# SCH_GSME_voltmeter_Arduino_ESP8266_TP405.net
KiCad netlist of a schematic drawn in EasyEDA
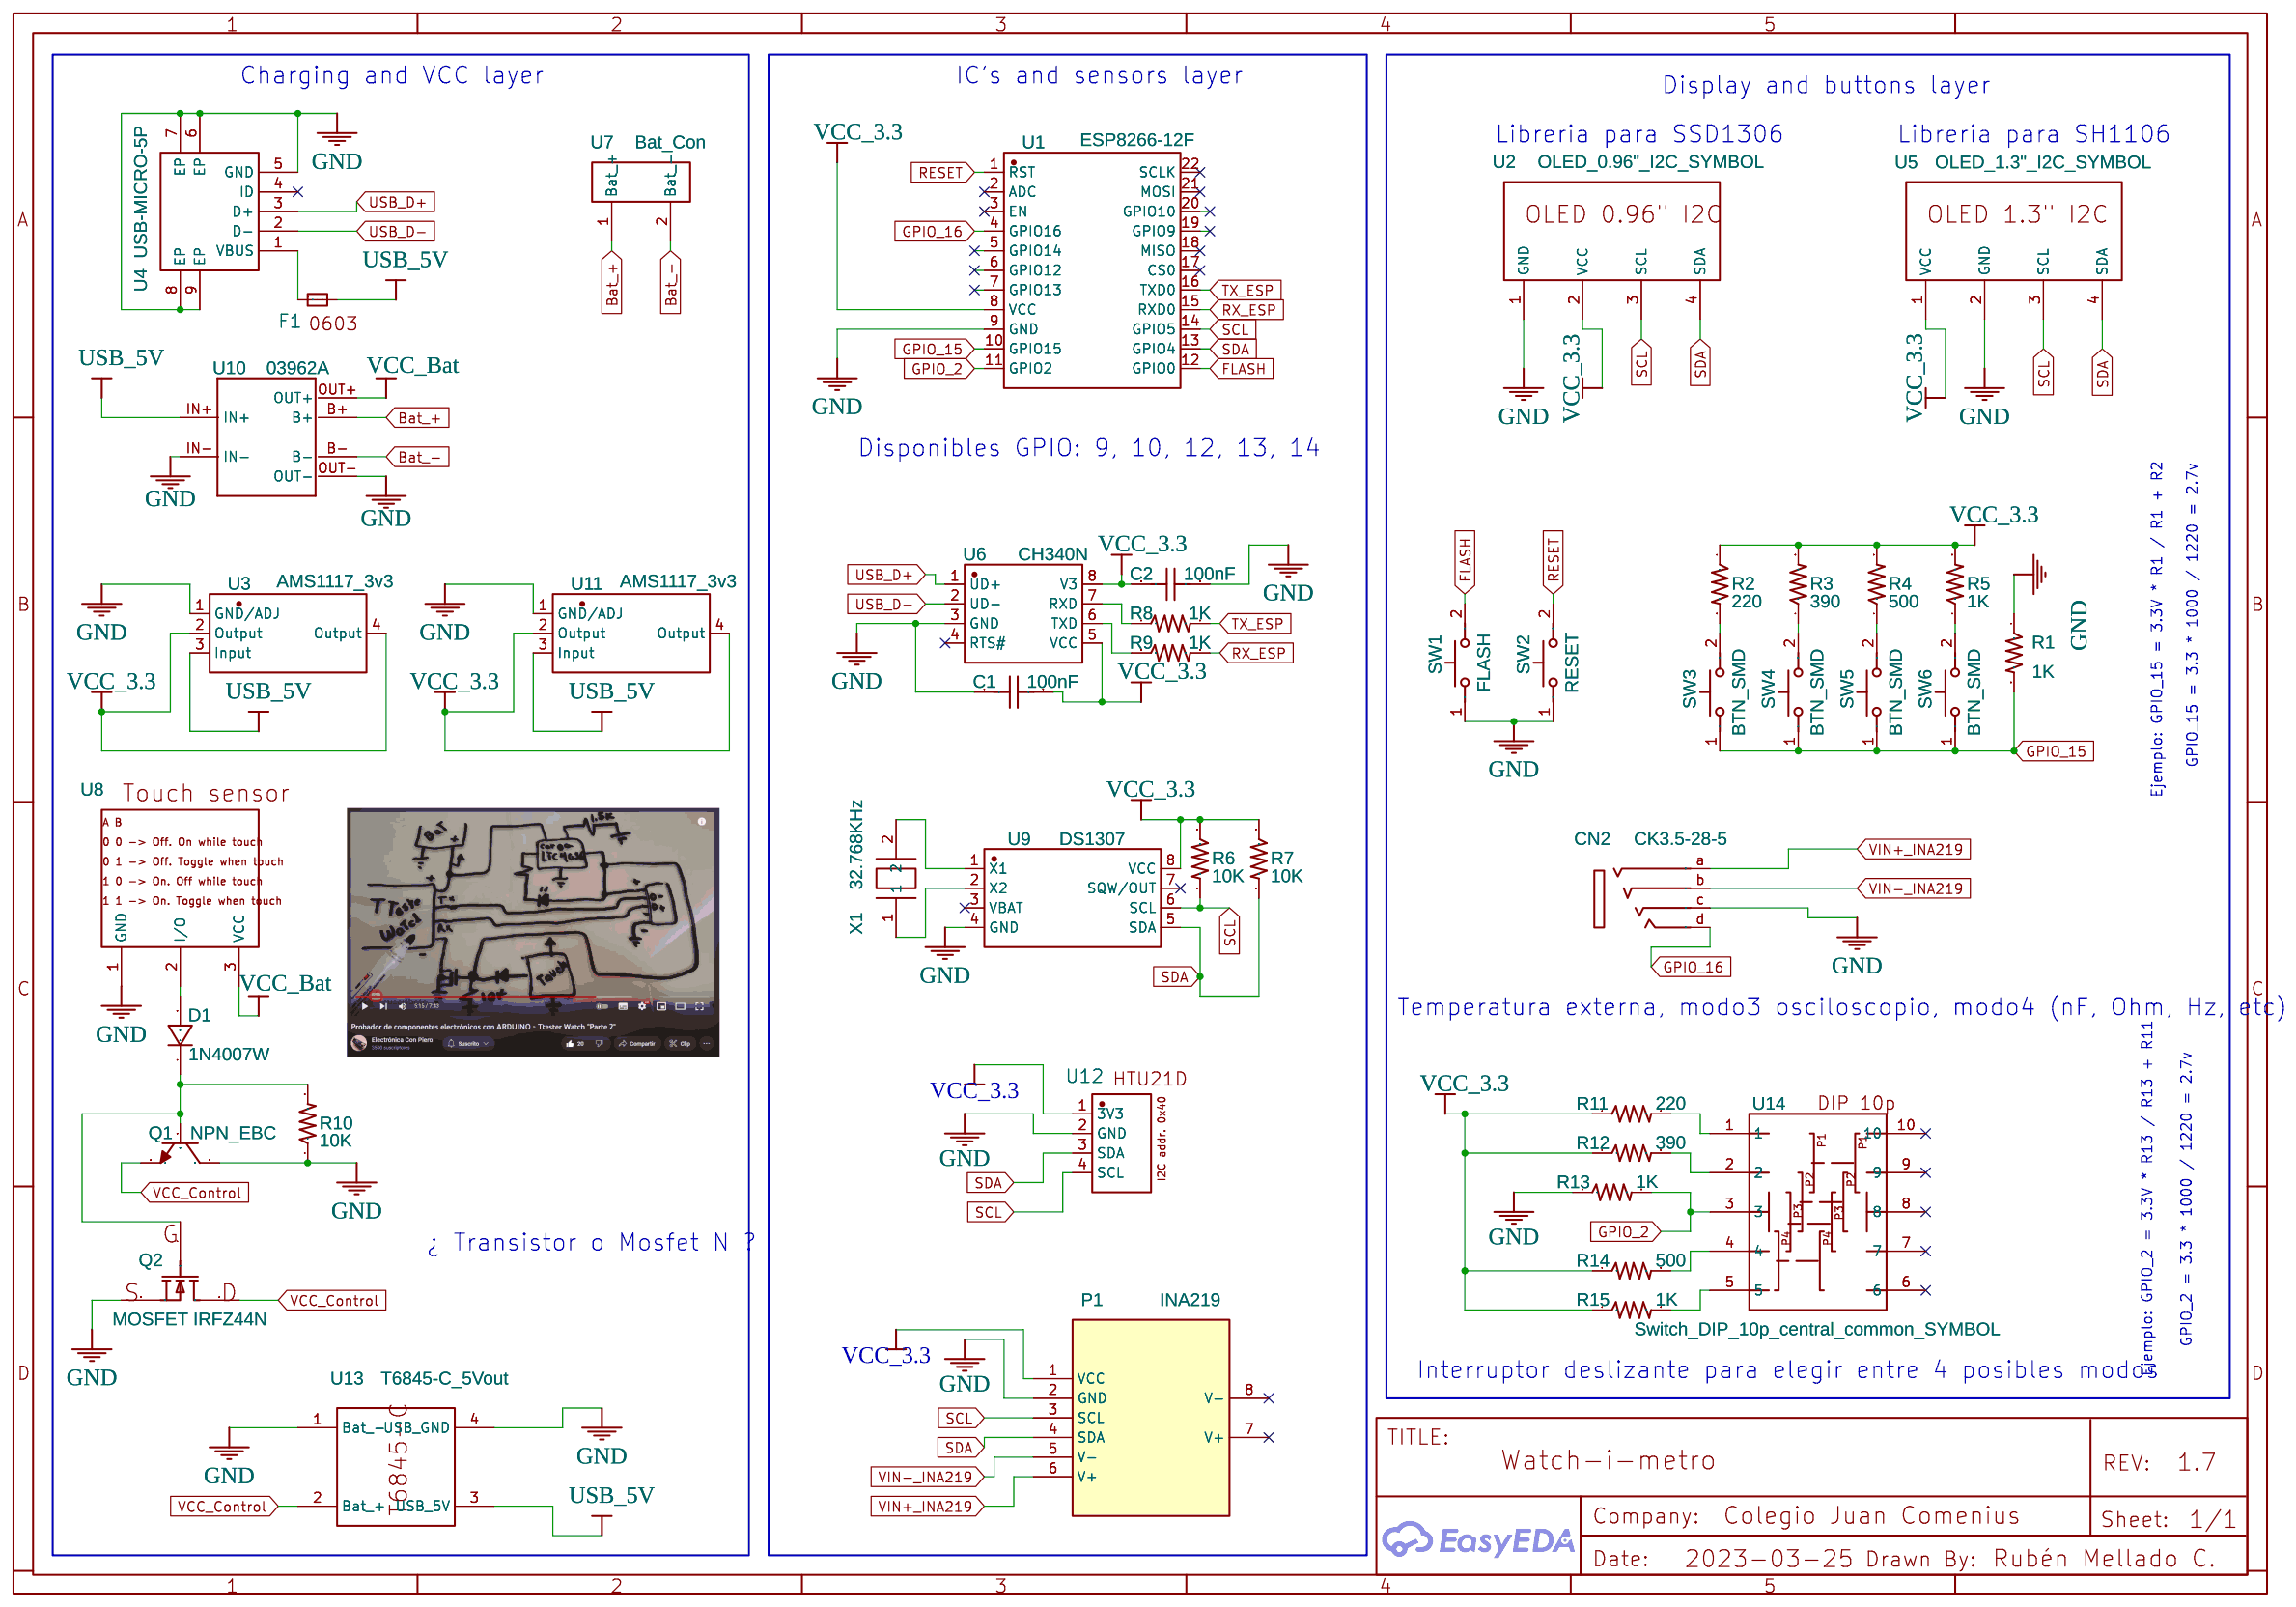
[diagram p0: schematic sheet]

(export (version "E")
  (design (tool "Eeschema 10.0.6"))
  (components
    (comp (ref "C1") (value "100nF") (libsource (lib "") (part "C_0603_US")))
    (comp (ref "C2") (value "100nF") (libsource (lib "") (part "C_0603_US")))
    (comp (ref "CN2")
      (value "CK3.5-28-5")
      (fields (field (name "BOM_Supplier Part") "C718048"))
      (libsource (lib "") (part "CK3.5-28-5"))
    )
    (comp (ref "D1")
      (value "1N4007W")
      (fields (field (name "BOM_Supplier Part") "C328592"))
      (libsource (lib "") (part "1N4007W"))
    )
    (comp (ref "F1")
      (value "Fuse")
      (fields (field (name "BOM_Manufacturer Part") "0603") (field (name "BOM_Supplier Part") "C9900014602"))
      (libsource (lib "") (part "0603_FUSE_SYMBOL"))
    )
    (comp (ref "P1") (value "INA219") (libsource (lib "") (part "INA219")))
    (comp (ref "Q1")
      (value "NPN_EBC")
      (fields
        (field (name "BOM_Manufacturer Part") "2n3904S-RTK/PS")
        (field (name "BOM_Supplier Part") "C18536")
      )
      (libsource (lib "") (part "2N3904(SOT-23)"))
    )
    (comp (ref "Q2") (value "MOSFET IRFZ44N") (libsource (lib "") (part "MOSFET IRFZ44N")))
    (comp (ref "R1") (value "1K") (libsource (lib "") (part "RESISTOR0603")))
    (comp (ref "R2") (value "220") (libsource (lib "") (part "RESISTOR0603")))
    (comp (ref "R3") (value "390") (libsource (lib "") (part "RESISTOR0603_1")))
    (comp (ref "R4") (value "500") (libsource (lib "") (part "RESISTOR0603_1")))
    (comp (ref "R5") (value "1K") (libsource (lib "") (part "RESISTOR0603_1")))
    (comp (ref "R6") (value "10K") (libsource (lib "") (part "RESISTOR0603")))
    (comp (ref "R7") (value "10K") (libsource (lib "") (part "RESISTOR0603")))
    (comp (ref "R8") (value "1K") (libsource (lib "") (part "RESISTOR0603_2")))
    (comp (ref "R9") (value "1K") (libsource (lib "") (part "RESISTOR0603_2")))
    (comp (ref "R10") (value "10K") (libsource (lib "") (part "RESISTOR0603_1")))
    (comp (ref "R11") (value "220") (libsource (lib "") (part "RESISTOR0603_2")))
    (comp (ref "R12") (value "390") (libsource (lib "") (part "RESISTOR0603_2")))
    (comp (ref "R13") (value "1K") (libsource (lib "") (part "RESISTOR0603_2")))
    (comp (ref "R14") (value "500") (libsource (lib "") (part "RESISTOR0603_2")))
    (comp (ref "R15") (value "1K") (libsource (lib "") (part "RESISTOR0603_2")))
    (comp (ref "SW1")
      (value "FLASH")
      (fields
        (field (name "BOM_Manufacturer Part") "BUTTON2")
        (field (name "BOM_Supplier Part") "C9900005988")
      )
      (libsource (lib "") (part "BUTTON2"))
    )
    (comp (ref "SW2")
      (value "RESET")
      (fields
        (field (name "BOM_Manufacturer Part") "BUTTON2")
        (field (name "BOM_Supplier Part") "C9900005988")
      )
      (libsource (lib "") (part "BUTTON2"))
    )
    (comp (ref "SW3")
      (value "BTN_SMD")
      (fields
        (field (name "BOM_Manufacturer Part") "BUTTON2")
        (field (name "BOM_Supplier Part") "C9900005988")
      )
      (libsource (lib "") (part "BUTTON2"))
    )
    (comp (ref "SW4")
      (value "BTN_SMD")
      (fields
        (field (name "BOM_Manufacturer Part") "BUTTON2")
        (field (name "BOM_Supplier Part") "C9900005988")
      )
      (libsource (lib "") (part "BUTTON2"))
    )
    (comp (ref "SW5")
      (value "BTN_SMD")
      (fields
        (field (name "BOM_Manufacturer Part") "BUTTON2")
        (field (name "BOM_Supplier Part") "C9900005988")
      )
      (libsource (lib "") (part "BUTTON2"))
    )
    (comp (ref "SW6")
      (value "BTN_SMD")
      (fields
        (field (name "BOM_Manufacturer Part") "BUTTON2")
        (field (name "BOM_Supplier Part") "C9900005988")
      )
      (libsource (lib "") (part "BUTTON2"))
    )
    (comp (ref "U1")
      (value "ESP8266-12F")
      (fields
        (field (name "BOM_Manufacturer Part") "ESP-12F(ESP8266MOD)")
        (field (name "BOM_Supplier Part") "C82891")
      )
      (libsource (lib "") (part "ESP-12F(ESP8266MOD)"))
    )
    (comp (ref "U2")
      (value "OLED_0.96\"_I2C_SYMBOL")
      (libsource (lib "") (part "OLED_0.96{dblquote}_I2C_SYMBOL"))
    )
    (comp (ref "U3")
      (value "AMS1117_3v3")
      (fields
        (field (name "BOM_Manufacturer Part") "AMS1117-3.3S")
        (field (name "BOM_Supplier Part") "C2842296")
      )
      (libsource (lib "") (part "AMS1117-3.3S"))
    )
    (comp (ref "U4")
      (value "USB-MICRO-5P")
      (fields
        (field (name "BOM_Manufacturer Part") "USB-Micro-5P")
        (field (name "BOM_Supplier Part") "C9900014288")
      )
      (libsource (lib "") (part "USB-MICRO-5P"))
    )
    (comp (ref "U5")
      (value "OLED_1.3\"_I2C_SYMBOL")
      (libsource (lib "") (part "OLED_1.3{dblquote}_I2C_SYMBOL"))
    )
    (comp (ref "U6")
      (value "CH340N")
      (fields (field (name "BOM_Supplier Part") "C506813"))
      (libsource (lib "") (part "CH340N"))
    )
    (comp (ref "U7") (value "Bat_Con") (libsource (lib "") (part "Connector_Battery_2_Wires_2p")))
    (comp (ref "U8") (value "Touch_Sensor") (libsource (lib "") (part "Touch_Sensor_3p_A_B_SYMBOL")))
    (comp (ref "U9")
      (value "DS1307")
      (fields
        (field (name "BOM_Manufacturer Part") "DS1307M/TR")
        (field (name "BOM_Supplier Part") "C356706")
      )
      (libsource (lib "") (part "DS1307M/TR"))
    )
    (comp (ref "U10") (value "03962A") (libsource (lib "") (part "03962A")))
    (comp (ref "U11")
      (value "AMS1117_3v3")
      (fields
        (field (name "BOM_Manufacturer Part") "AMS1117-3.3S")
        (field (name "BOM_Supplier Part") "C2842296")
      )
      (libsource (lib "") (part "AMS1117-3.3S"))
    )
    (comp (ref "U12") (value "HTU21D") (libsource (lib "") (part "SF HTU21D HUMIDITY")))
    (comp (ref "U13") (value "T6845-C_5Vout") (libsource (lib "") (part "T6845-C_powerbank_module_SYMBOL")))
    (comp (ref "U14")
      (value "Switch_DIP_10p_central_common_SYMBOL")
      (libsource (lib "") (part "Switch_DIP_10p_central_common_SYMBOL"))
    )
    (comp (ref "X1") (value "32.768KHz") (libsource (lib "") (part "Quartz_X_2p_Symbol")))
  )
  (nets
    (net (code "1") (name "Bat_+") (class "Default")
      (node (ref "U10") (pin "B+") (pinfunction "B+_B+") (pintype "bidirectional"))
      (node (ref "U7") (pin "1") (pinfunction "Bat_+_1") (pintype "unspecified"))
    )
    (net (code "2") (name "Bat_-") (class "Default")
      (node (ref "U10") (pin "B-") (pinfunction "B-_B-") (pintype "bidirectional"))
      (node (ref "U7") (pin "2") (pinfunction "Bat_-_2") (pintype "unspecified"))
    )
    (net (code "3") (name "FLASH") (class "Default")
      (node (ref "SW1") (pin "2") (pinfunction "2_2") (pintype "unspecified"))
      (node (ref "U1") (pin "12") (pinfunction "GPIO0_12") (pintype "unspecified"))
    )
    (net (code "4") (name "GND") (class "Default")
      (node (ref "C1") (pin "1") (pinfunction "1_1") (pintype "unspecified"))
      (node (ref "C2") (pin "2") (pinfunction "2_2") (pintype "unspecified"))
      (node (ref "CN2") (pin "c") (pinfunction "c_c") (pintype "unspecified"))
      (node (ref "P1") (pin "2") (pinfunction "GND_2") (pintype "unspecified"))
      (node (ref "Q1") (pin "2") (pinfunction "C_2") (pintype "input"))
      (node (ref "Q2") (pin "3") (pinfunction "S_3") (pintype "unspecified"))
      (node (ref "R1") (pin "1") (pinfunction "1_1") (pintype "unspecified"))
      (node (ref "R10") (pin "1") (pinfunction "1_1") (pintype "unspecified"))
      (node (ref "R13") (pin "1") (pinfunction "1_1") (pintype "unspecified"))
      (node (ref "SW1") (pin "1") (pinfunction "1_1") (pintype "unspecified"))
      (node (ref "SW2") (pin "1") (pinfunction "1_1") (pintype "unspecified"))
      (node (ref "U1") (pin "9") (pinfunction "GND_9") (pintype "unspecified"))
      (node (ref "U10") (pin "IN-") (pinfunction "IN-_IN-") (pintype "bidirectional"))
      (node (ref "U10") (pin "OUT-") (pinfunction "OUT-_OUT-") (pintype "bidirectional"))
      (node (ref "U11") (pin "1") (pinfunction "GND/ADJ_1") (pintype "unspecified"))
      (node (ref "U12") (pin "2") (pinfunction "GND_2") (pintype "unspecified"))
      (node (ref "U13") (pin "1") (pinfunction "Bat_-_1") (pintype "unspecified"))
      (node (ref "U13") (pin "4") (pinfunction "USB_GND_4") (pintype "unspecified"))
      (node (ref "U2") (pin "1") (pinfunction "GND_1") (pintype "unspecified"))
      (node (ref "U3") (pin "1") (pinfunction "GND/ADJ_1") (pintype "unspecified"))
      (node (ref "U4") (pin "5") (pinfunction "GND_5") (pintype "unspecified"))
      (node (ref "U4") (pin "6") (pinfunction "EP_6") (pintype "unspecified"))
      (node (ref "U4") (pin "7") (pinfunction "EP_7") (pintype "unspecified"))
      (node (ref "U4") (pin "8") (pinfunction "EP_8") (pintype "unspecified"))
      (node (ref "U4") (pin "9") (pinfunction "EP_9") (pintype "unspecified"))
      (node (ref "U5") (pin "2") (pinfunction "GND_2") (pintype "unspecified"))
      (node (ref "U6") (pin "3") (pinfunction "GND_3") (pintype "unspecified"))
      (node (ref "U8") (pin "1") (pinfunction "GND_1") (pintype "unspecified"))
      (node (ref "U9") (pin "4") (pinfunction "GND_4") (pintype "unspecified"))
    )
    (net (code "5") (name "GPIO_2") (class "Default")
      (node (ref "R13") (pin "2") (pinfunction "2_2") (pintype "unspecified"))
      (node (ref "U1") (pin "11") (pinfunction "GPIO2_11") (pintype "unspecified"))
      (node (ref "U14") (pin "3") (pinfunction "3_3") (pintype "unspecified"))
    )
    (net (code "6") (name "GPIO_15") (class "Default")
      (node (ref "R1") (pin "2") (pinfunction "2_2") (pintype "unspecified"))
      (node (ref "SW3") (pin "1") (pinfunction "1_1") (pintype "unspecified"))
      (node (ref "SW4") (pin "1") (pinfunction "1_1") (pintype "unspecified"))
      (node (ref "SW5") (pin "1") (pinfunction "1_1") (pintype "unspecified"))
      (node (ref "SW6") (pin "1") (pinfunction "1_1") (pintype "unspecified"))
      (node (ref "U1") (pin "10") (pinfunction "GPIO15_10") (pintype "unspecified"))
    )
    (net (code "7") (name "GPIO_16") (class "Default")
      (node (ref "CN2") (pin "d") (pinfunction "d_d") (pintype "unspecified"))
      (node (ref "U1") (pin "4") (pinfunction "GPIO16_4") (pintype "unspecified"))
    )
    (net (code "8") (name "Net-(F1-K)") (class "Default")
      (node (ref "F1") (pin "1") (pinfunction "K_1") (pintype "unspecified"))
      (node (ref "U4") (pin "1") (pinfunction "VBUS_1") (pintype "unspecified"))
    )
    (net (code "9") (name "Net-(Q1-B)") (class "Default")
      (node (ref "D1") (pin "1") (pinfunction "1_1") (pintype "unspecified"))
      (node (ref "Q1") (pin "3") (pinfunction "B_3") (pintype "input"))
      (node (ref "Q2") (pin "1") (pinfunction "G_1") (pintype "unspecified"))
      (node (ref "R10") (pin "2") (pinfunction "2_2") (pintype "unspecified"))
    )
    (net (code "10") (name "Net-(R2-Pad2)") (class "Default")
      (node (ref "R2") (pin "2") (pinfunction "2_2") (pintype "unspecified"))
      (node (ref "SW3") (pin "2") (pinfunction "2_2") (pintype "unspecified"))
    )
    (net (code "11") (name "Net-(R3-Pad1)") (class "Default")
      (node (ref "R3") (pin "1") (pinfunction "1_1") (pintype "unspecified"))
      (node (ref "SW4") (pin "2") (pinfunction "2_2") (pintype "unspecified"))
    )
    (net (code "12") (name "Net-(R4-Pad1)") (class "Default")
      (node (ref "R4") (pin "1") (pinfunction "1_1") (pintype "unspecified"))
      (node (ref "SW5") (pin "2") (pinfunction "2_2") (pintype "unspecified"))
    )
    (net (code "13") (name "Net-(R5-Pad1)") (class "Default")
      (node (ref "R5") (pin "1") (pinfunction "1_1") (pintype "unspecified"))
      (node (ref "SW6") (pin "2") (pinfunction "2_2") (pintype "unspecified"))
    )
    (net (code "14") (name "Net-(R11-Pad2)") (class "Default")
      (node (ref "R11") (pin "2") (pinfunction "2_2") (pintype "unspecified"))
      (node (ref "U14") (pin "1") (pinfunction "1_1") (pintype "unspecified"))
    )
    (net (code "15") (name "Net-(R12-Pad2)") (class "Default")
      (node (ref "R12") (pin "2") (pinfunction "2_2") (pintype "unspecified"))
      (node (ref "U14") (pin "2") (pinfunction "2_2") (pintype "unspecified"))
    )
    (net (code "16") (name "Net-(R14-Pad2)") (class "Default")
      (node (ref "R14") (pin "2") (pinfunction "2_2") (pintype "unspecified"))
      (node (ref "U14") (pin "4") (pinfunction "4_4") (pintype "unspecified"))
    )
    (net (code "17") (name "Net-(R15-Pad2)") (class "Default")
      (node (ref "R15") (pin "2") (pinfunction "2_2") (pintype "unspecified"))
      (node (ref "U14") (pin "5") (pinfunction "5_5") (pintype "unspecified"))
    )
    (net (code "18") (name "Net-(U6-RXD)") (class "Default")
      (node (ref "R8") (pin "1") (pinfunction "1_1") (pintype "unspecified"))
      (node (ref "U6") (pin "7") (pinfunction "RXD_7") (pintype "unspecified"))
    )
    (net (code "19") (name "Net-(U6-TXD)") (class "Default")
      (node (ref "R9") (pin "1") (pinfunction "1_1") (pintype "unspecified"))
      (node (ref "U6") (pin "6") (pinfunction "TXD_6") (pintype "unspecified"))
    )
    (net (code "20") (name "Net-(U8-I{slash}O)") (class "Default")
      (node (ref "D1") (pin "2") (pinfunction "2_2") (pintype "unspecified"))
      (node (ref "U8") (pin "2") (pinfunction "I/O_2") (pintype "unspecified"))
    )
    (net (code "21") (name "Net-(U9-X1)") (class "Default")
      (node (ref "U9") (pin "1") (pinfunction "X1_1") (pintype "unspecified"))
      (node (ref "X1") (pin "2") (pinfunction "2_2") (pintype "unspecified"))
    )
    (net (code "22") (name "Net-(U9-X2)") (class "Default")
      (node (ref "U9") (pin "2") (pinfunction "X2_2") (pintype "unspecified"))
      (node (ref "X1") (pin "1") (pinfunction "1_1") (pintype "unspecified"))
    )
    (net (code "23") (name "RESET") (class "Default")
      (node (ref "SW2") (pin "2") (pinfunction "2_2") (pintype "unspecified"))
      (node (ref "U1") (pin "1") (pinfunction "RST_1") (pintype "unspecified"))
    )
    (net (code "24") (name "RX_ESP") (class "Default")
      (node (ref "R9") (pin "2") (pinfunction "2_2") (pintype "unspecified"))
      (node (ref "U1") (pin "15") (pinfunction "RXD0_15") (pintype "unspecified"))
    )
    (net (code "25") (name "SCL") (class "Default")
      (node (ref "P1") (pin "3") (pinfunction "SCL_3") (pintype "unspecified"))
      (node (ref "R6") (pin "2") (pinfunction "2_2") (pintype "unspecified"))
      (node (ref "U1") (pin "14") (pinfunction "GPIO5_14") (pintype "unspecified"))
      (node (ref "U12") (pin "4") (pinfunction "SCL_4") (pintype "unspecified"))
      (node (ref "U2") (pin "3") (pinfunction "SCL_3") (pintype "unspecified"))
      (node (ref "U5") (pin "3") (pinfunction "SCL_3") (pintype "unspecified"))
      (node (ref "U9") (pin "6") (pinfunction "SCL_6") (pintype "unspecified"))
    )
    (net (code "26") (name "SDA") (class "Default")
      (node (ref "P1") (pin "4") (pinfunction "SDA_4") (pintype "unspecified"))
      (node (ref "R7") (pin "2") (pinfunction "2_2") (pintype "unspecified"))
      (node (ref "U1") (pin "13") (pinfunction "GPIO4_13") (pintype "unspecified"))
      (node (ref "U12") (pin "3") (pinfunction "SDA_3") (pintype "unspecified"))
      (node (ref "U2") (pin "4") (pinfunction "SDA_4") (pintype "unspecified"))
      (node (ref "U5") (pin "4") (pinfunction "SDA_4") (pintype "unspecified"))
      (node (ref "U9") (pin "5") (pinfunction "SDA_5") (pintype "unspecified"))
    )
    (net (code "27") (name "TX_ESP") (class "Default")
      (node (ref "R8") (pin "2") (pinfunction "2_2") (pintype "unspecified"))
      (node (ref "U1") (pin "16") (pinfunction "TXD0_16") (pintype "unspecified"))
    )
    (net (code "28") (name "USB_5V") (class "Default")
      (node (ref "F1") (pin "2") (pinfunction "A_2") (pintype "unspecified"))
      (node (ref "U10") (pin "IN+") (pinfunction "IN+_IN+") (pintype "bidirectional"))
      (node (ref "U11") (pin "3") (pinfunction "Input_3") (pintype "unspecified"))
      (node (ref "U13") (pin "3") (pinfunction "USB_5V_3") (pintype "unspecified"))
      (node (ref "U3") (pin "3") (pinfunction "Input_3") (pintype "unspecified"))
    )
    (net (code "29") (name "USB_D+") (class "Default")
      (node (ref "U4") (pin "3") (pinfunction "D+_3") (pintype "unspecified"))
      (node (ref "U6") (pin "1") (pinfunction "UD+_1") (pintype "unspecified"))
    )
    (net (code "30") (name "USB_D-") (class "Default")
      (node (ref "U4") (pin "2") (pinfunction "D-_2") (pintype "unspecified"))
      (node (ref "U6") (pin "2") (pinfunction "UD-_2") (pintype "unspecified"))
    )
    (net (code "31") (name "VCC_3.3") (class "Default")
      (node (ref "C1") (pin "2") (pinfunction "2_2") (pintype "unspecified"))
      (node (ref "C2") (pin "1") (pinfunction "1_1") (pintype "unspecified"))
      (node (ref "P1") (pin "1") (pinfunction "VCC_1") (pintype "unspecified"))
      (node (ref "R11") (pin "1") (pinfunction "1_1") (pintype "unspecified"))
      (node (ref "R12") (pin "1") (pinfunction "1_1") (pintype "unspecified"))
      (node (ref "R14") (pin "1") (pinfunction "1_1") (pintype "unspecified"))
      (node (ref "R15") (pin "1") (pinfunction "1_1") (pintype "unspecified"))
      (node (ref "R2") (pin "1") (pinfunction "1_1") (pintype "unspecified"))
      (node (ref "R3") (pin "2") (pinfunction "2_2") (pintype "unspecified"))
      (node (ref "R4") (pin "2") (pinfunction "2_2") (pintype "unspecified"))
      (node (ref "R5") (pin "2") (pinfunction "2_2") (pintype "unspecified"))
      (node (ref "R6") (pin "1") (pinfunction "1_1") (pintype "unspecified"))
      (node (ref "R7") (pin "1") (pinfunction "1_1") (pintype "unspecified"))
      (node (ref "U1") (pin "8") (pinfunction "VCC_8") (pintype "unspecified"))
      (node (ref "U11") (pin "2") (pinfunction "Output_2") (pintype "unspecified"))
      (node (ref "U11") (pin "4") (pinfunction "Output_4") (pintype "unspecified"))
      (node (ref "U12") (pin "1") (pinfunction "3V3_1") (pintype "unspecified"))
      (node (ref "U2") (pin "2") (pinfunction "VCC_2") (pintype "unspecified"))
      (node (ref "U3") (pin "2") (pinfunction "Output_2") (pintype "unspecified"))
      (node (ref "U3") (pin "4") (pinfunction "Output_4") (pintype "unspecified"))
      (node (ref "U5") (pin "1") (pinfunction "VCC_1") (pintype "unspecified"))
      (node (ref "U6") (pin "5") (pinfunction "VCC_5") (pintype "unspecified"))
      (node (ref "U6") (pin "8") (pinfunction "V3_8") (pintype "unspecified"))
      (node (ref "U9") (pin "8") (pinfunction "VCC_8") (pintype "unspecified"))
    )
    (net (code "32") (name "VCC_Bat") (class "Default")
      (node (ref "U10") (pin "OUT+") (pinfunction "OUT+_OUT+") (pintype "bidirectional"))
      (node (ref "U8") (pin "3") (pinfunction "VCC_3") (pintype "unspecified"))
    )
    (net (code "33") (name "VCC_Control") (class "Default")
      (node (ref "Q1") (pin "1") (pinfunction "E_1") (pintype "input"))
      (node (ref "Q2") (pin "2") (pinfunction "D_2") (pintype "unspecified"))
      (node (ref "U13") (pin "2") (pinfunction "Bat_+_2") (pintype "unspecified"))
    )
    (net (code "34") (name "VIN+_INA219") (class "Default")
      (node (ref "CN2") (pin "a") (pinfunction "a_a") (pintype "unspecified"))
      (node (ref "P1") (pin "6") (pinfunction "V+_6") (pintype "unspecified"))
    )
    (net (code "35") (name "VIN-_INA219") (class "Default")
      (node (ref "CN2") (pin "b") (pinfunction "b_b") (pintype "unspecified"))
      (node (ref "P1") (pin "5") (pinfunction "V-_5") (pintype "unspecified"))
    )
    (net (code "36") (name "unconnected-(P1-V+-Pad7)") (class "Default")
      (node (ref "P1") (pin "7") (pinfunction "V+_7") (pintype "unspecified+no_connect"))
    )
    (net (code "37") (name "unconnected-(P1-V--Pad8)") (class "Default")
      (node (ref "P1") (pin "8") (pinfunction "V-_8") (pintype "unspecified+no_connect"))
    )
    (net (code "38") (name "unconnected-(U1-ADC-Pad2)") (class "Default")
      (node (ref "U1") (pin "2") (pinfunction "ADC_2") (pintype "unspecified+no_connect"))
    )
    (net (code "39") (name "unconnected-(U1-CS0-Pad17)") (class "Default")
      (node (ref "U1") (pin "17") (pinfunction "CS0_17") (pintype "unspecified+no_connect"))
    )
    (net (code "40") (name "unconnected-(U1-EN-Pad3)") (class "Default")
      (node (ref "U1") (pin "3") (pinfunction "EN_3") (pintype "unspecified+no_connect"))
    )
    (net (code "41") (name "unconnected-(U1-GPIO9-Pad19)") (class "Default")
      (node (ref "U1") (pin "19") (pinfunction "GPIO9_19") (pintype "unspecified+no_connect"))
    )
    (net (code "42") (name "unconnected-(U1-GPIO10-Pad20)") (class "Default")
      (node (ref "U1") (pin "20") (pinfunction "GPIO10_20") (pintype "unspecified+no_connect"))
    )
    (net (code "43") (name "unconnected-(U1-GPIO12-Pad6)") (class "Default")
      (node (ref "U1") (pin "6") (pinfunction "GPIO12_6") (pintype "unspecified+no_connect"))
    )
    (net (code "44") (name "unconnected-(U1-GPIO13-Pad7)") (class "Default")
      (node (ref "U1") (pin "7") (pinfunction "GPIO13_7") (pintype "unspecified+no_connect"))
    )
    (net (code "45") (name "unconnected-(U1-GPIO14-Pad5)") (class "Default")
      (node (ref "U1") (pin "5") (pinfunction "GPIO14_5") (pintype "unspecified+no_connect"))
    )
    (net (code "46") (name "unconnected-(U1-MISO-Pad18)") (class "Default")
      (node (ref "U1") (pin "18") (pinfunction "MISO_18") (pintype "unspecified+no_connect"))
    )
    (net (code "47") (name "unconnected-(U1-MOSI-Pad21)") (class "Default")
      (node (ref "U1") (pin "21") (pinfunction "MOSI_21") (pintype "unspecified+no_connect"))
    )
    (net (code "48") (name "unconnected-(U1-SCLK-Pad22)") (class "Default")
      (node (ref "U1") (pin "22") (pinfunction "SCLK_22") (pintype "unspecified+no_connect"))
    )
    (net (code "49") (name "unconnected-(U4-ID-Pad4)") (class "Default")
      (node (ref "U4") (pin "4") (pinfunction "ID_4") (pintype "unspecified+no_connect"))
    )
    (net (code "50") (name "unconnected-(U6-RTS#-Pad4)") (class "Default")
      (node (ref "U6") (pin "4") (pinfunction "RTS#_4") (pintype "unspecified+no_connect"))
    )
    (net (code "51") (name "unconnected-(U9-SQW{slash}OUT-Pad7)") (class "Default")
      (node (ref "U9") (pin "7") (pinfunction "SQW/OUT_7") (pintype "unspecified+no_connect"))
    )
    (net (code "52") (name "unconnected-(U9-VBAT-Pad3)") (class "Default")
      (node (ref "U9") (pin "3") (pinfunction "VBAT_3") (pintype "unspecified+no_connect"))
    )
    (net (code "53") (name "unconnected-(U14-Pad6)") (class "Default")
      (node (ref "U14") (pin "6") (pinfunction "6_6") (pintype "unspecified+no_connect"))
    )
    (net (code "54") (name "unconnected-(U14-Pad7)") (class "Default")
      (node (ref "U14") (pin "7") (pinfunction "7_7") (pintype "unspecified+no_connect"))
    )
    (net (code "55") (name "unconnected-(U14-Pad8)") (class "Default")
      (node (ref "U14") (pin "8") (pinfunction "8_8") (pintype "unspecified+no_connect"))
    )
    (net (code "56") (name "unconnected-(U14-Pad9)") (class "Default")
      (node (ref "U14") (pin "9") (pinfunction "9_9") (pintype "unspecified+no_connect"))
    )
    (net (code "57") (name "unconnected-(U14-Pad10)") (class "Default")
      (node (ref "U14") (pin "10") (pinfunction "10_10") (pintype "unspecified+no_connect"))
    )
  )
)
